# Adafruit_2_7in_Sharp_Memory_Display.net
KiCad netlist of a schematic drawn in Altium Designer
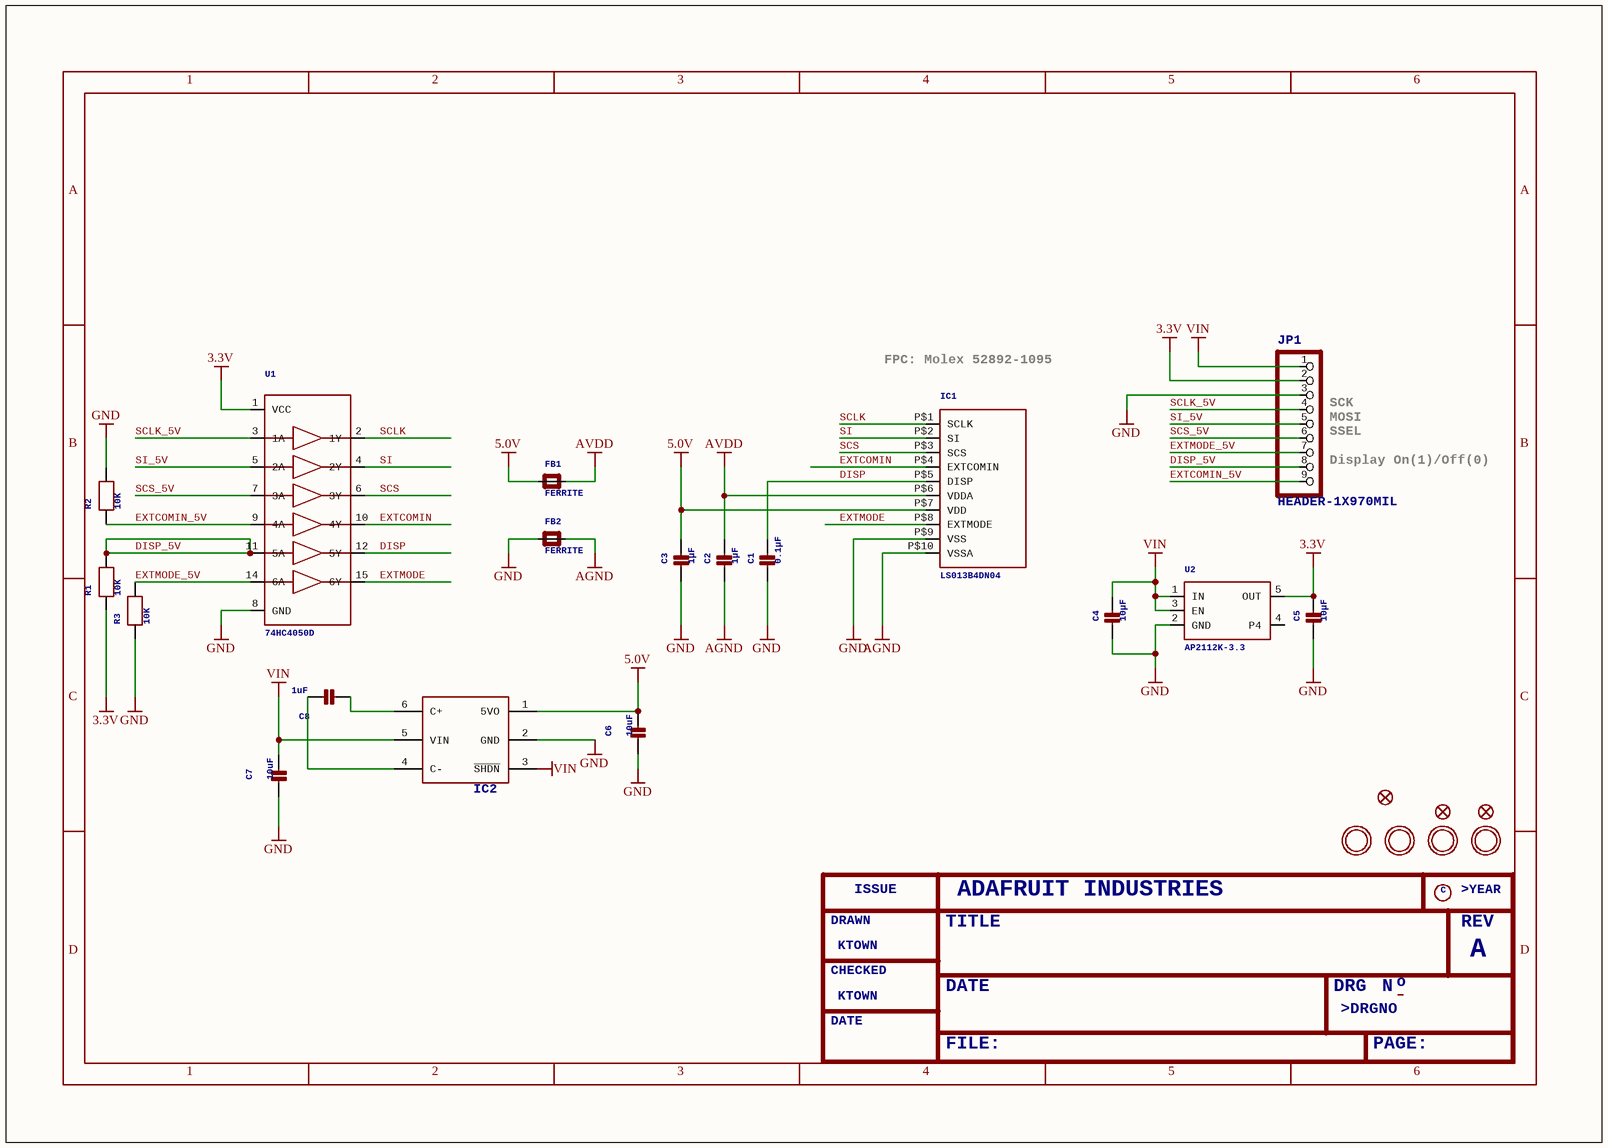
[diagram p0: Adafruit 2.7in Sharp Memory Display.SchDoc]

(export (version "E")
  (design (tool "Eeschema 10.0.6"))
  (components
    (comp (ref "C1")
      (value "0.1µF")
      (footprint "0603-NO")
      (libsource (lib "microbuilder") (part "CAP_CERAMIC0603_NO"))
    )
    (comp (ref "C2")
      (value "1µF")
      (footprint "0805_10MGAP")
      (libsource (lib "microbuilder") (part "CAP_CERAMIC0805_10MGAP"))
    )
    (comp (ref "C3")
      (value "1µF")
      (footprint "0805-NO")
      (libsource (lib "") (part "CAP_CERAMIC0805-NOOUTLINE_1"))
    )
    (comp (ref "C4")
      (value "10µF")
      (footprint "0805-NO")
      (libsource (lib "") (part "CAP_CERAMIC0805-NOOUTLINE_1"))
    )
    (comp (ref "C5")
      (value "10µF")
      (footprint "0805-NO")
      (libsource (lib "") (part "CAP_CERAMIC0805-NOOUTLINE_1"))
    )
    (comp (ref "C6")
      (value "10uF")
      (footprint "0805-NO")
      (libsource (lib "") (part "CAP_CERAMIC0805-NOOUTLINE_1"))
    )
    (comp (ref "C7")
      (value "10uF")
      (footprint "0805-NO")
      (libsource (lib "") (part "CAP_CERAMIC0805-NOOUTLINE_1"))
    )
    (comp (ref "C8")
      (value "1uF")
      (footprint "0805-NO")
      (libsource (lib "microbuilder") (part "CAP_CERAMIC0805-NOOUTLINE"))
    )
    (comp (ref "FB1")
      (value "FERRITE")
      (footprint "_0805")
      (libsource (lib "microbuilder") (part "FERRITE_0805"))
    )
    (comp (ref "FB2")
      (value "FERRITE")
      (footprint "_0805")
      (libsource (lib "microbuilder") (part "FERRITE_0805"))
    )
    (comp (ref "FID1")
      (value "FIDUCIAL_1MM")
      (footprint "FIDUCIAL_1MM")
      (description "Fiducial Alignment Points   Various fiducial points for machine vision alignment.")
      (libsource (lib "microbuilder") (part "FIDUCIAL_1MM"))
    )
    (comp (ref "FID2")
      (value "FIDUCIAL_1MM")
      (footprint "FIDUCIAL_1MM")
      (description "Fiducial Alignment Points   Various fiducial points for machine vision alignment.")
      (libsource (lib "microbuilder") (part "FIDUCIAL_1MM"))
    )
    (comp (ref "FID3")
      (value "FIDUCIAL_1MM")
      (footprint "FIDUCIAL_1MM")
      (description "Fiducial Alignment Points   Various fiducial points for machine vision alignment.")
      (libsource (lib "microbuilder") (part "FIDUCIAL_1MM"))
    )
    (comp (ref "IC1")
      (value "LS013B4DN04")
      (footprint "SHARP_2.7IN")
      (libsource (lib "adafruit_display") (part "DISP_EINK_SHARPMEMORYLCD_10PIN_27IN"))
    )
    (comp (ref "IC2") (value "AP3602") (footprint "SOT23-6") (libsource (lib "microbuilder") (part "AP3602")))
    (comp (ref "JP1")
      (value "HEADER-1X970MIL")
      (footprint "1X09_ROUND_70")
      (description "PIN HEADER")
      (libsource (lib "microbuilder") (part "HEADER-1X970MIL"))
    )
    (comp (ref "R1")
      (value "10K")
      (footprint "0603-NO")
      (libsource (lib "microbuilder") (part "RESISTOR_0603_NOOUT"))
    )
    (comp (ref "R2")
      (value "10K")
      (footprint "0603-NO")
      (libsource (lib "microbuilder") (part "RESISTOR_0603_NOOUT"))
    )
    (comp (ref "R3")
      (value "10K")
      (footprint "0603-NO")
      (libsource (lib "microbuilder") (part "RESISTOR_0603_NOOUT"))
    )
    (comp (ref "U$21")
      (value "MOUNTINGHOLE2.5_THICK")
      (footprint "MOUNTINGHOLE_2.5_PLATED_THICK")
      (description "Mounting Hole   For #2 screws (0.086\"/2.18mm width, 0.094\"/2.4mm hole) use 2.5mm")
      (libsource (lib "microbuilder") (part "MOUNTINGHOLE2.5_THICK"))
    )
    (comp (ref "U$22")
      (value "MOUNTINGHOLE2.5_THICK")
      (footprint "MOUNTINGHOLE_2.5_PLATED_THICK")
      (description "Mounting Hole   For #2 screws (0.086\"/2.18mm width, 0.094\"/2.4mm hole) use 2.5mm")
      (libsource (lib "microbuilder") (part "MOUNTINGHOLE2.5_THICK"))
    )
    (comp (ref "U$27")
      (value "MOUNTINGHOLE2.5")
      (footprint "MOUNTINGHOLE_2.5_PLATED")
      (description "Mounting Hole   For #2 screws (0.086\"/2.18mm width, 0.094\"/2.4mm hole) use 2.5mm")
      (libsource (lib "microbuilder") (part "MOUNTINGHOLE2.5"))
    )
    (comp (ref "U$28")
      (value "MOUNTINGHOLE2.5")
      (footprint "MOUNTINGHOLE_2.5_PLATED")
      (description "Mounting Hole   For #2 screws (0.086\"/2.18mm width, 0.094\"/2.4mm hole) use 2.5mm")
      (libsource (lib "microbuilder") (part "MOUNTINGHOLE2.5"))
    )
    (comp (ref "U1")
      (value "74HC4050D")
      (footprint "SOIC16")
      (libsource (lib "microbuilder") (part "74HC4050D"))
    )
    (comp (ref "U2")
      (value "AP2112K-3.3")
      (footprint "SOT23-5")
      (libsource (lib "adafruit_power") (part "VREG_SOT23-5"))
    )
  )
  (nets
    (net (code "1") (name "/DISP") (class "Default")
      (node (ref "C1") (pin "1") (pinfunction "1_1") (pintype "passive"))
      (node (ref "IC1") (pin "P$5") (pinfunction "DISP_P$5") (pintype "passive"))
      (node (ref "U1") (pin "12") (pinfunction "5Y_12") (pintype "passive"))
    )
    (net (code "2") (name "/DISP_5V") (class "Default")
      (node (ref "JP1") (pin "8") (pinfunction "8_8") (pintype "passive"))
      (node (ref "R1") (pin "2") (pinfunction "2_2") (pintype "passive"))
      (node (ref "U1") (pin "11") (pinfunction "5A_11") (pintype "passive"))
    )
    (net (code "3") (name "/EXTCOMIN") (class "Default")
      (node (ref "IC1") (pin "P$4") (pinfunction "EXTCOMIN_P$4") (pintype "passive"))
      (node (ref "U1") (pin "10") (pinfunction "4Y_10") (pintype "passive"))
    )
    (net (code "4") (name "/EXTCOMIN_5V") (class "Default")
      (node (ref "JP1") (pin "9") (pinfunction "9_9") (pintype "passive"))
      (node (ref "R2") (pin "1") (pinfunction "1_1") (pintype "passive"))
      (node (ref "U1") (pin "9") (pinfunction "4A_9") (pintype "passive"))
    )
    (net (code "5") (name "/EXTMODE") (class "Default")
      (node (ref "IC1") (pin "P$8") (pinfunction "EXTMODE_P$8") (pintype "passive"))
      (node (ref "U1") (pin "15") (pinfunction "6Y_15") (pintype "passive"))
    )
    (net (code "6") (name "/EXTMODE_5V") (class "Default")
      (node (ref "JP1") (pin "7") (pinfunction "7_7") (pintype "passive"))
      (node (ref "R3") (pin "2") (pinfunction "2_2") (pintype "passive"))
      (node (ref "U1") (pin "14") (pinfunction "6A_14") (pintype "passive"))
    )
    (net (code "7") (name "/SCLK") (class "Default")
      (node (ref "IC1") (pin "P$1") (pinfunction "SCLK_P$1") (pintype "passive"))
      (node (ref "U1") (pin "2") (pinfunction "1Y_2") (pintype "passive"))
    )
    (net (code "8") (name "/SCLK_5V") (class "Default")
      (node (ref "JP1") (pin "4") (pinfunction "4_4") (pintype "passive"))
      (node (ref "U1") (pin "3") (pinfunction "1A_3") (pintype "passive"))
    )
    (net (code "9") (name "/SCS") (class "Default")
      (node (ref "IC1") (pin "P$3") (pinfunction "SCS_P$3") (pintype "passive"))
      (node (ref "U1") (pin "6") (pinfunction "3Y_6") (pintype "passive"))
    )
    (net (code "10") (name "/SCS_5V") (class "Default")
      (node (ref "JP1") (pin "6") (pinfunction "6_6") (pintype "passive"))
      (node (ref "U1") (pin "7") (pinfunction "3A_7") (pintype "passive"))
    )
    (net (code "11") (name "/SI") (class "Default")
      (node (ref "IC1") (pin "P$2") (pinfunction "SI_P$2") (pintype "passive"))
      (node (ref "U1") (pin "4") (pinfunction "2Y_4") (pintype "passive"))
    )
    (net (code "12") (name "/SI_5V") (class "Default")
      (node (ref "JP1") (pin "5") (pinfunction "5_5") (pintype "passive"))
      (node (ref "U1") (pin "5") (pinfunction "2A_5") (pintype "passive"))
    )
    (net (code "13") (name "3.3V") (class "Default")
      (node (ref "C5") (pin "1") (pinfunction "1_1") (pintype "passive"))
      (node (ref "JP1") (pin "2") (pinfunction "2_2") (pintype "passive"))
      (node (ref "R1") (pin "1") (pinfunction "1_1") (pintype "passive"))
      (node (ref "U1") (pin "1") (pinfunction "VCC_1") (pintype "passive"))
      (node (ref "U2") (pin "5") (pinfunction "OUT_5") (pintype "open_emitter"))
    )
    (net (code "14") (name "5.0V") (class "Default")
      (node (ref "C3") (pin "1") (pinfunction "1_1") (pintype "passive"))
      (node (ref "C6") (pin "1") (pinfunction "1_1") (pintype "passive"))
      (node (ref "FB1") (pin "1") (pinfunction "P$1_1") (pintype "passive"))
      (node (ref "IC1") (pin "P$7") (pinfunction "VDD_P$7") (pintype "power_in"))
      (node (ref "IC2") (pin "1") (pinfunction "5VO_1") (pintype "open_emitter"))
    )
    (net (code "15") (name "AGND") (class "Default")
      (node (ref "C2") (pin "2") (pinfunction "2_2") (pintype "passive"))
      (node (ref "FB2") (pin "2") (pinfunction "P$2_2") (pintype "passive"))
      (node (ref "IC1") (pin "P$10") (pinfunction "VSSA_P$10") (pintype "power_in"))
    )
    (net (code "16") (name "AVDD") (class "Default")
      (node (ref "C2") (pin "1") (pinfunction "1_1") (pintype "passive"))
      (node (ref "FB1") (pin "2") (pinfunction "P$2_2") (pintype "passive"))
      (node (ref "IC1") (pin "P$6") (pinfunction "VDDA_P$6") (pintype "power_in"))
    )
    (net (code "17") (name "GND") (class "Default")
      (node (ref "C1") (pin "2") (pinfunction "2_2") (pintype "passive"))
      (node (ref "C3") (pin "2") (pinfunction "2_2") (pintype "passive"))
      (node (ref "C4") (pin "2") (pinfunction "2_2") (pintype "passive"))
      (node (ref "C5") (pin "2") (pinfunction "2_2") (pintype "passive"))
      (node (ref "C6") (pin "2") (pinfunction "2_2") (pintype "passive"))
      (node (ref "C7") (pin "2") (pinfunction "2_2") (pintype "passive"))
      (node (ref "FB2") (pin "1") (pinfunction "P$1_1") (pintype "passive"))
      (node (ref "IC1") (pin "P$9") (pinfunction "VSS_P$9") (pintype "power_in"))
      (node (ref "IC2") (pin "2") (pinfunction "GND_2") (pintype "power_in"))
      (node (ref "JP1") (pin "3") (pinfunction "3_3") (pintype "passive"))
      (node (ref "R2") (pin "2") (pinfunction "2_2") (pintype "passive"))
      (node (ref "R3") (pin "1") (pinfunction "1_1") (pintype "passive"))
      (node (ref "U1") (pin "8") (pinfunction "GND_8") (pintype "passive"))
      (node (ref "U2") (pin "2") (pinfunction "GND_2") (pintype "power_in"))
    )
    (net (code "18") (name "Net-(IC2-C+)") (class "Default")
      (node (ref "C8") (pin "2") (pinfunction "2_2") (pintype "passive"))
      (node (ref "IC2") (pin "6") (pinfunction "C+_6") (pintype "passive"))
    )
    (net (code "19") (name "Net-(IC2-C-)") (class "Default")
      (node (ref "C8") (pin "1") (pinfunction "1_1") (pintype "passive"))
      (node (ref "IC2") (pin "4") (pinfunction "C-_4") (pintype "passive"))
    )
    (net (code "20") (name "VIN") (class "Default")
      (node (ref "C4") (pin "1") (pinfunction "1_1") (pintype "passive"))
      (node (ref "C7") (pin "1") (pinfunction "1_1") (pintype "passive"))
      (node (ref "IC2") (pin "3") (pinfunction "~{SHDN}_3") (pintype "passive"))
      (node (ref "IC2") (pin "5") (pinfunction "VIN_5") (pintype "power_in"))
      (node (ref "JP1") (pin "1") (pinfunction "1_1") (pintype "passive"))
      (node (ref "U2") (pin "1") (pinfunction "IN_1") (pintype "power_in"))
      (node (ref "U2") (pin "3") (pinfunction "EN_3") (pintype "passive"))
    )
    (net (code "21") (name "unconnected-(U2-P4-Pad4)") (class "Default")
      (node (ref "U2") (pin "4") (pinfunction "P4_4") (pintype "passive"))
    )
  )
)
